# Relay_block_v1_circuit_diagram.net
KiCad netlist of a schematic drawn in EAGLE
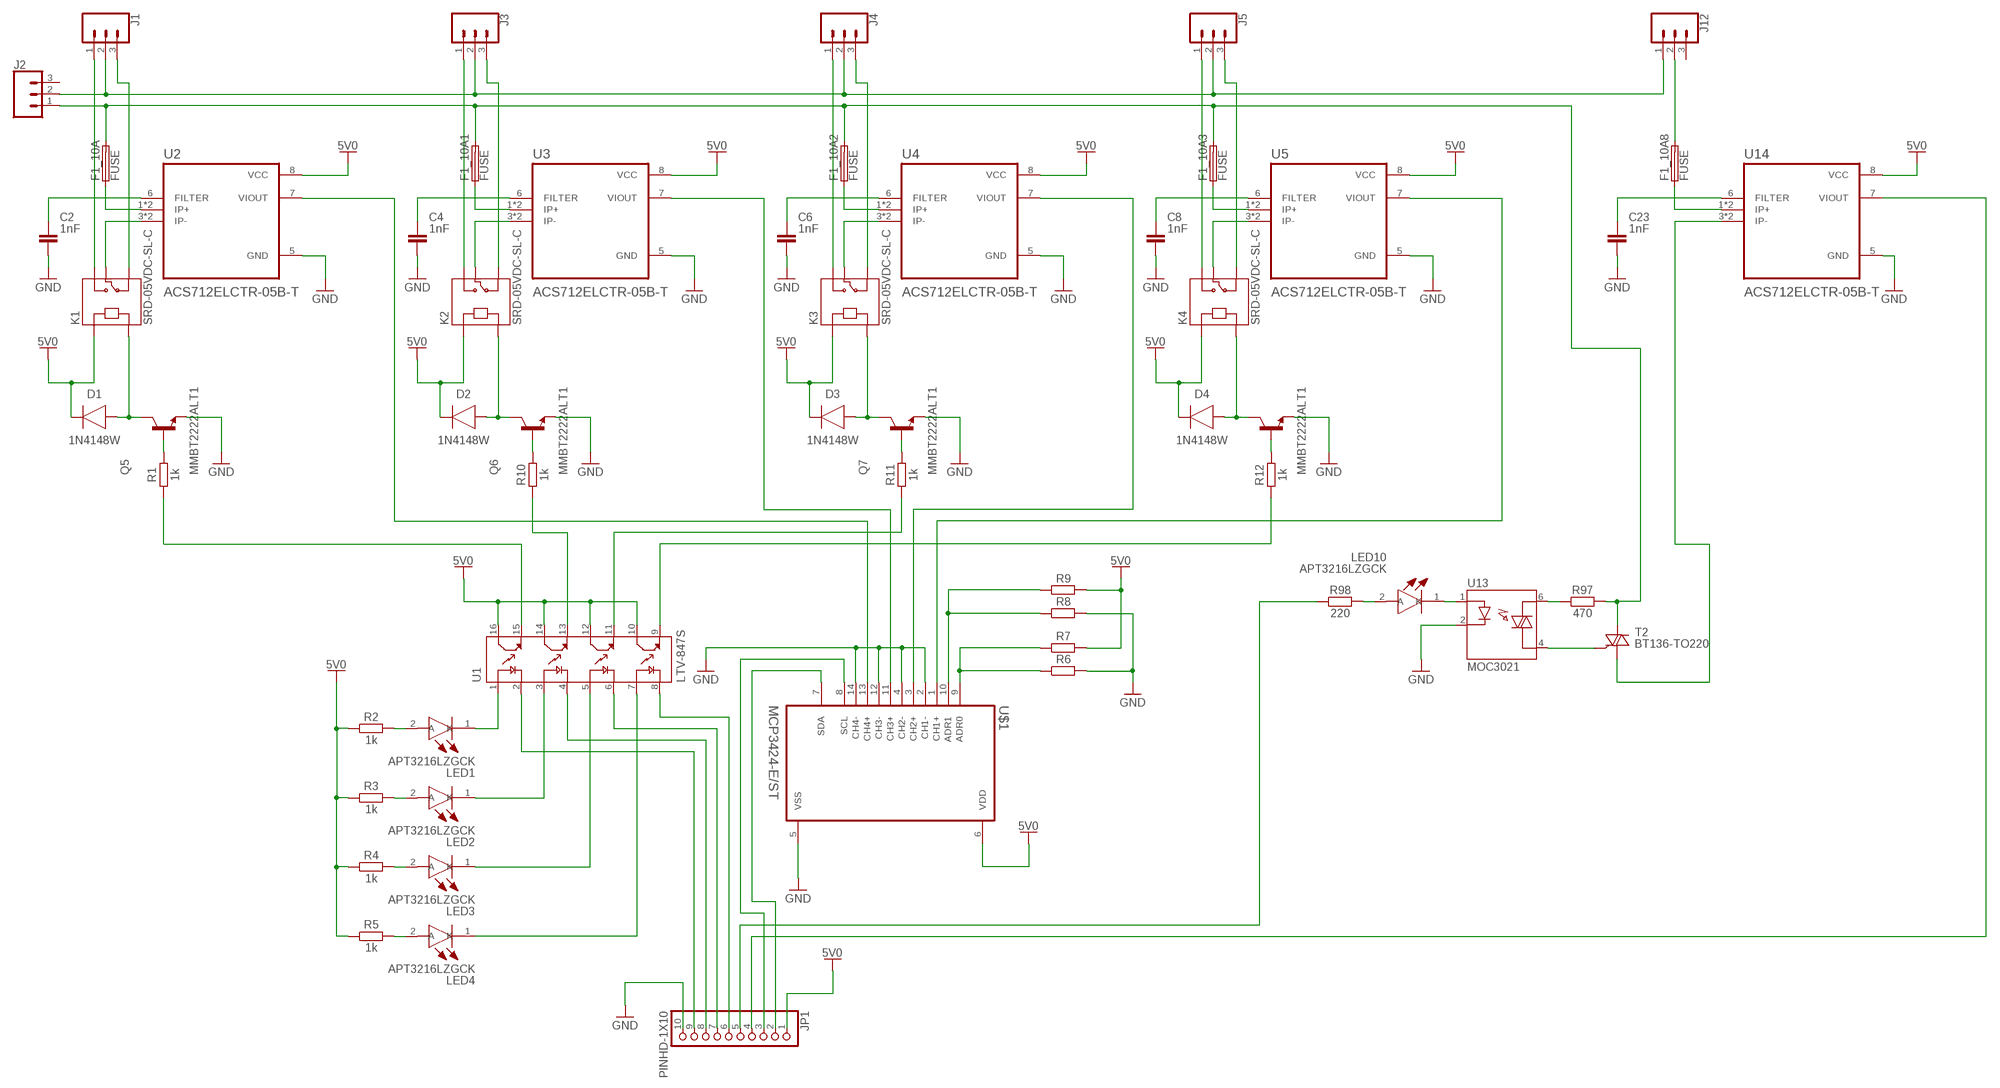
[diagram p0: schematic, sheet 1]

(export (version "E")
  (design (tool "Eeschema 10.0.6"))
  (components
    (comp (ref "C2")
      (value "1nF")
      (footprint "eagle-import:CAPC3216X135")
      (libsource (lib "eagle-import") (part "CCHIP-1206(3216-METRIC)_"))
    )
    (comp (ref "C4")
      (value "1nF")
      (footprint "eagle-import:CAPC3216X135")
      (libsource (lib "eagle-import") (part "CCHIP-1206(3216-METRIC)_"))
    )
    (comp (ref "C6")
      (value "1nF")
      (footprint "eagle-import:CAPC3216X135")
      (libsource (lib "eagle-import") (part "CCHIP-1206(3216-METRIC)_"))
    )
    (comp (ref "C8")
      (value "1nF")
      (footprint "eagle-import:CAPC3216X135")
      (libsource (lib "eagle-import") (part "CCHIP-1206(3216-METRIC)_"))
    )
    (comp (ref "C23")
      (value "1nF")
      (footprint "eagle-import:CAPC3216X135")
      (libsource (lib "eagle-import") (part "CCHIP-1206(3216-METRIC)_"))
    )
    (comp (ref "D1")
      (value "1N4148W")
      (footprint "eagle-import:SOD3715X135")
      (fields (field (name "MANUFACTURER") "Diodes Incorporated"))
      (libsource (lib "eagle-import") (part "DIODE__SOD123G1N4148W-7-F"))
    )
    (comp (ref "D2")
      (value "1N4148W")
      (footprint "eagle-import:SOD3715X135")
      (fields (field (name "MANUFACTURER") "Diodes Incorporated"))
      (libsource (lib "eagle-import") (part "DIODE__SOD123G1N4148W-7-F"))
    )
    (comp (ref "D3")
      (value "1N4148W")
      (footprint "eagle-import:SOD3715X135")
      (fields (field (name "MANUFACTURER") "Diodes Incorporated"))
      (libsource (lib "eagle-import") (part "DIODE__SOD123G1N4148W-7-F"))
    )
    (comp (ref "D4")
      (value "1N4148W")
      (footprint "eagle-import:SOD3715X135")
      (fields (field (name "MANUFACTURER") "Diodes Incorporated"))
      (libsource (lib "eagle-import") (part "DIODE__SOD123G1N4148W-7-F"))
    )
    (comp (ref "F1_10A")
      (value "FUSE")
      (footprint "eagle-import:FUSC3215X82N")
      (libsource (lib "eagle-import") (part "FUSECHIP-1206(3216-METRIC)_"))
    )
    (comp (ref "F1_10A1")
      (value "FUSE")
      (footprint "eagle-import:FUSC3215X82N")
      (libsource (lib "eagle-import") (part "FUSECHIP-1206(3216-METRIC)_"))
    )
    (comp (ref "F1_10A2")
      (value "FUSE")
      (footprint "eagle-import:FUSC3215X82N")
      (libsource (lib "eagle-import") (part "FUSECHIP-1206(3216-METRIC)_"))
    )
    (comp (ref "F1_10A3")
      (value "FUSE")
      (footprint "eagle-import:FUSC3215X82N")
      (libsource (lib "eagle-import") (part "FUSECHIP-1206(3216-METRIC)_"))
    )
    (comp (ref "F1_10A8")
      (value "FUSE")
      (footprint "eagle-import:FUSC3215X82N")
      (libsource (lib "eagle-import") (part "FUSECHIP-1206(3216-METRIC)_"))
    )
    (comp (ref "J1")
      (value "CONN_03-SCREW-5MM")
      (footprint "eagle-import:SCREWTERMINAL-5MM-3")
      (libsource (lib "eagle-import") (part "CONN_03-SCREW-5MM"))
    )
    (comp (ref "J2")
      (value "CONN_03-SCREW-5MM")
      (footprint "eagle-import:SCREWTERMINAL-5MM-3")
      (libsource (lib "eagle-import") (part "CONN_03-SCREW-5MM"))
    )
    (comp (ref "J3")
      (value "CONN_03-SCREW-5MM")
      (footprint "eagle-import:SCREWTERMINAL-5MM-3")
      (libsource (lib "eagle-import") (part "CONN_03-SCREW-5MM"))
    )
    (comp (ref "J4")
      (value "CONN_03-SCREW-5MM")
      (footprint "eagle-import:SCREWTERMINAL-5MM-3")
      (libsource (lib "eagle-import") (part "CONN_03-SCREW-5MM"))
    )
    (comp (ref "J5")
      (value "CONN_03-SCREW-5MM")
      (footprint "eagle-import:SCREWTERMINAL-5MM-3")
      (libsource (lib "eagle-import") (part "CONN_03-SCREW-5MM"))
    )
    (comp (ref "J12")
      (value "CONN_03-SCREW-5MM")
      (footprint "eagle-import:SCREWTERMINAL-5MM-3")
      (libsource (lib "eagle-import") (part "CONN_03-SCREW-5MM"))
    )
    (comp (ref "JP1")
      (value "PINHD-1X10")
      (footprint "eagle-import:1X10")
      (libsource (lib "eagle-import") (part "PINHD-1X10"))
    )
    (comp (ref "K1")
      (value "SRD-05VDC-SL-C")
      (footprint "eagle-import:RELAY_SRD-05VDC-SL-C")
      (fields (field (name "MANUFACTURER") "SONGLE RELAY"))
      (libsource (lib "eagle-import") (part "SRD-05VDC-SL-C"))
    )
    (comp (ref "K2")
      (value "SRD-05VDC-SL-C")
      (footprint "eagle-import:RELAY_SRD-05VDC-SL-C")
      (fields (field (name "MANUFACTURER") "SONGLE RELAY"))
      (libsource (lib "eagle-import") (part "SRD-05VDC-SL-C"))
    )
    (comp (ref "K3")
      (value "SRD-05VDC-SL-C")
      (footprint "eagle-import:RELAY_SRD-05VDC-SL-C")
      (fields (field (name "MANUFACTURER") "SONGLE RELAY"))
      (libsource (lib "eagle-import") (part "SRD-05VDC-SL-C"))
    )
    (comp (ref "K4")
      (value "SRD-05VDC-SL-C")
      (footprint "eagle-import:RELAY_SRD-05VDC-SL-C")
      (fields (field (name "MANUFACTURER") "SONGLE RELAY"))
      (libsource (lib "eagle-import") (part "SRD-05VDC-SL-C"))
    )
    (comp (ref "LED1")
      (value "APT3216LZGCK")
      (footprint "eagle-import:LEDC3216X95N")
      (fields (field (name "MOUSER_PART_NUMBER") "604-APT3216LZGCK"))
      (libsource (lib "eagle-import") (part "APT3216LZGCK"))
    )
    (comp (ref "LED2")
      (value "APT3216LZGCK")
      (footprint "eagle-import:LEDC3216X95N")
      (fields (field (name "MOUSER_PART_NUMBER") "604-APT3216LZGCK"))
      (libsource (lib "eagle-import") (part "APT3216LZGCK"))
    )
    (comp (ref "LED3")
      (value "APT3216LZGCK")
      (footprint "eagle-import:LEDC3216X95N")
      (fields (field (name "MOUSER_PART_NUMBER") "604-APT3216LZGCK"))
      (libsource (lib "eagle-import") (part "APT3216LZGCK"))
    )
    (comp (ref "LED4")
      (value "APT3216LZGCK")
      (footprint "eagle-import:LEDC3216X95N")
      (fields (field (name "MOUSER_PART_NUMBER") "604-APT3216LZGCK"))
      (libsource (lib "eagle-import") (part "APT3216LZGCK"))
    )
    (comp (ref "LED10")
      (value "APT3216LZGCK")
      (footprint "eagle-import:LEDC3216X95N")
      (fields (field (name "MOUSER_PART_NUMBER") "604-APT3216LZGCK"))
      (libsource (lib "eagle-import") (part "APT3216LZGCK"))
    )
    (comp (ref "Q5")
      (value "MMBT2222ALT1")
      (footprint "eagle-import:SOT95P237X111-3N")
      (fields (field (name "MF") "ON Semiconductor"))
      (libsource (lib "eagle-import") (part "MMBT2222ALT1"))
    )
    (comp (ref "Q6")
      (value "MMBT2222ALT1")
      (footprint "eagle-import:SOT95P237X111-3N")
      (fields (field (name "MF") "ON Semiconductor"))
      (libsource (lib "eagle-import") (part "MMBT2222ALT1"))
    )
    (comp (ref "Q7")
      (value "MMBT2222ALT1")
      (footprint "eagle-import:SOT95P237X111-3N")
      (fields (field (name "MF") "ON Semiconductor"))
      (libsource (lib "eagle-import") (part "MMBT2222ALT1"))
    )
    (comp (ref "Q8")
      (value "MMBT2222ALT1")
      (footprint "eagle-import:SOT95P237X111-3N")
      (fields (field (name "MF") "ON Semiconductor"))
      (libsource (lib "eagle-import") (part "MMBT2222ALT1"))
    )
    (comp (ref "R1")
      (value "1k")
      (footprint "eagle-import:RESC3216X70")
      (libsource (lib "eagle-import") (part "RCHIP-1206(3216-METRIC)_"))
    )
    (comp (ref "R2")
      (value "1k")
      (footprint "eagle-import:RESC3216X70")
      (libsource (lib "eagle-import") (part "RCHIP-1206(3216-METRIC)_"))
    )
    (comp (ref "R3")
      (value "1k")
      (footprint "eagle-import:RESC3216X70")
      (libsource (lib "eagle-import") (part "RCHIP-1206(3216-METRIC)_"))
    )
    (comp (ref "R4")
      (value "1k")
      (footprint "eagle-import:RESC3216X70")
      (libsource (lib "eagle-import") (part "RCHIP-1206(3216-METRIC)_"))
    )
    (comp (ref "R5")
      (value "1k")
      (footprint "eagle-import:RESC3216X70")
      (libsource (lib "eagle-import") (part "RCHIP-1206(3216-METRIC)_"))
    )
    (comp (ref "R6")
      (value "R_CHIP-1206(3216-METRIC)")
      (footprint "eagle-import:RESC3216X70")
      (libsource (lib "eagle-import") (part "RCHIP-1206(3216-METRIC)_"))
    )
    (comp (ref "R7")
      (value "R_CHIP-1206(3216-METRIC)")
      (footprint "eagle-import:RESC3216X70")
      (libsource (lib "eagle-import") (part "RCHIP-1206(3216-METRIC)_"))
    )
    (comp (ref "R8")
      (value "R_CHIP-1206(3216-METRIC)")
      (footprint "eagle-import:RESC3216X70")
      (libsource (lib "eagle-import") (part "RCHIP-1206(3216-METRIC)_"))
    )
    (comp (ref "R9")
      (value "R_CHIP-1206(3216-METRIC)")
      (footprint "eagle-import:RESC3216X70")
      (libsource (lib "eagle-import") (part "RCHIP-1206(3216-METRIC)_"))
    )
    (comp (ref "R10")
      (value "1k")
      (footprint "eagle-import:RESC3216X70")
      (libsource (lib "eagle-import") (part "RCHIP-1206(3216-METRIC)_"))
    )
    (comp (ref "R11")
      (value "1k")
      (footprint "eagle-import:RESC3216X70")
      (libsource (lib "eagle-import") (part "RCHIP-1206(3216-METRIC)_"))
    )
    (comp (ref "R12")
      (value "1k")
      (footprint "eagle-import:RESC3216X70")
      (libsource (lib "eagle-import") (part "RCHIP-1206(3216-METRIC)_"))
    )
    (comp (ref "R97")
      (value "470")
      (footprint "eagle-import:RESC3216X70")
      (libsource (lib "eagle-import") (part "RCHIP-1206(3216-METRIC)_"))
    )
    (comp (ref "R98")
      (value "220")
      (footprint "eagle-import:RESC3216X70")
      (libsource (lib "eagle-import") (part "RCHIP-1206(3216-METRIC)_"))
    )
    (comp (ref "T2")
      (value "BT136-TO220")
      (footprint "eagle-import:TO220AB")
      (fields (field (name "MF") "Rectron") (field (name "MP") "BT136"))
      (libsource (lib "eagle-import") (part "BT136-TO220"))
    )
    (comp (ref "U$1")
      (value "MCP3424-E/ST")
      (footprint "eagle-import:SOP65P640X120-14N")
      (libsource (lib "eagle-import") (part "MCP3424-E/ST"))
    )
    (comp (ref "U1")
      (value "LTV-847S")
      (footprint "eagle-import:SOIC254P1016X460-16N")
      (fields (field (name "MANUFACTURER") "LITE-ON Technology"))
      (libsource (lib "eagle-import") (part "LTV-847S"))
    )
    (comp (ref "U2")
      (value "ACS712ELCTR-05B-T")
      (footprint "eagle-import:SOIC127P600X175-8N")
      (libsource (lib "eagle-import") (part "ACS712ELCTR-05B-T"))
    )
    (comp (ref "U3")
      (value "ACS712ELCTR-05B-T")
      (footprint "eagle-import:SOIC127P600X175-8N")
      (libsource (lib "eagle-import") (part "ACS712ELCTR-05B-T"))
    )
    (comp (ref "U4")
      (value "ACS712ELCTR-05B-T")
      (footprint "eagle-import:SOIC127P600X175-8N")
      (libsource (lib "eagle-import") (part "ACS712ELCTR-05B-T"))
    )
    (comp (ref "U5")
      (value "ACS712ELCTR-05B-T")
      (footprint "eagle-import:SOIC127P600X175-8N")
      (libsource (lib "eagle-import") (part "ACS712ELCTR-05B-T"))
    )
    (comp (ref "U13")
      (value "MOC3021")
      (footprint "eagle-import:DIP762W45P254L889H508Q6")
      (fields (field (name "MF") "Lite-On"))
      (libsource (lib "eagle-import") (part "MOC3021"))
    )
    (comp (ref "U14")
      (value "ACS712ELCTR-05B-T")
      (footprint "eagle-import:SOIC127P600X175-8N")
      (libsource (lib "eagle-import") (part "ACS712ELCTR-05B-T"))
    )
  )
  (nets
    (net (code "1") (name "5V0") (class "Default")
      (node (ref "D1") (pin "1") (pinfunction "C_1") (pintype "passive"))
      (node (ref "D2") (pin "1") (pinfunction "C_1") (pintype "passive"))
      (node (ref "D3") (pin "1") (pinfunction "C_1") (pintype "passive"))
      (node (ref "D4") (pin "1") (pinfunction "C_1") (pintype "passive"))
      (node (ref "JP1") (pin "1") (pinfunction "1_1") (pintype "passive"))
      (node (ref "K1") (pin "A1") (pinfunction "A1_A1") (pintype "passive"))
      (node (ref "K2") (pin "A1") (pinfunction "A1_A1") (pintype "passive"))
      (node (ref "K3") (pin "A1") (pinfunction "A1_A1") (pintype "passive"))
      (node (ref "K4") (pin "A1") (pinfunction "A1_A1") (pintype "passive"))
      (node (ref "R2") (pin "1") (pinfunction "1_1") (pintype "passive"))
      (node (ref "R3") (pin "1") (pinfunction "1_1") (pintype "passive"))
      (node (ref "R4") (pin "1") (pinfunction "1_1") (pintype "passive"))
      (node (ref "R5") (pin "1") (pinfunction "1_1") (pintype "passive"))
      (node (ref "R7") (pin "2") (pinfunction "2_2") (pintype "passive"))
      (node (ref "R9") (pin "2") (pinfunction "2_2") (pintype "passive"))
      (node (ref "U$1") (pin "6") (pinfunction "VDD_6") (pintype "power_in"))
      (node (ref "U1") (pin "10") (pinfunction "CT3_10") (pintype "passive"))
      (node (ref "U1") (pin "12") (pinfunction "CT2_12") (pintype "passive"))
      (node (ref "U1") (pin "14") (pinfunction "CT1_14") (pintype "passive"))
      (node (ref "U1") (pin "16") (pinfunction "CT_16") (pintype "passive"))
      (node (ref "U14") (pin "8") (pinfunction "VCC_8") (pintype "power_in"))
      (node (ref "U2") (pin "8") (pinfunction "VCC_8") (pintype "power_in"))
      (node (ref "U3") (pin "8") (pinfunction "VCC_8") (pintype "power_in"))
      (node (ref "U4") (pin "8") (pinfunction "VCC_8") (pintype "power_in"))
      (node (ref "U5") (pin "8") (pinfunction "VCC_8") (pintype "power_in"))
    )
    (net (code "2") (name "GND") (class "Default")
      (node (ref "C2") (pin "2") (pinfunction "2_2") (pintype "passive"))
      (node (ref "C23") (pin "2") (pinfunction "2_2") (pintype "passive"))
      (node (ref "C4") (pin "2") (pinfunction "2_2") (pintype "passive"))
      (node (ref "C6") (pin "2") (pinfunction "2_2") (pintype "passive"))
      (node (ref "C8") (pin "2") (pinfunction "2_2") (pintype "passive"))
      (node (ref "JP1") (pin "10") (pinfunction "10_10") (pintype "passive"))
      (node (ref "Q5") (pin "2") (pinfunction "E_2") (pintype "passive"))
      (node (ref "Q6") (pin "2") (pinfunction "E_2") (pintype "passive"))
      (node (ref "Q7") (pin "2") (pinfunction "E_2") (pintype "passive"))
      (node (ref "Q8") (pin "2") (pinfunction "E_2") (pintype "passive"))
      (node (ref "R6") (pin "2") (pinfunction "2_2") (pintype "passive"))
      (node (ref "R8") (pin "2") (pinfunction "2_2") (pintype "passive"))
      (node (ref "U$1") (pin "12") (pinfunction "CH3-_12") (pintype "input"))
      (node (ref "U$1") (pin "14") (pinfunction "CH4-_14") (pintype "input"))
      (node (ref "U$1") (pin "2") (pinfunction "CH1-_2") (pintype "input"))
      (node (ref "U$1") (pin "4") (pinfunction "CH2-_4") (pintype "input"))
      (node (ref "U$1") (pin "5") (pinfunction "VSS_5") (pintype "power_in"))
      (node (ref "U13") (pin "2") (pinfunction "CATODE_2") (pintype "passive"))
      (node (ref "U14") (pin "5") (pinfunction "GND_5") (pintype "power_in"))
      (node (ref "U2") (pin "5") (pinfunction "GND_5") (pintype "power_in"))
      (node (ref "U3") (pin "5") (pinfunction "GND_5") (pintype "power_in"))
      (node (ref "U4") (pin "5") (pinfunction "GND_5") (pintype "power_in"))
      (node (ref "U5") (pin "5") (pinfunction "GND_5") (pintype "power_in"))
    )
    (net (code "3") (name "Net-(D1-A)") (class "Default")
      (node (ref "D1") (pin "2") (pinfunction "A_2") (pintype "passive"))
      (node (ref "K1") (pin "A2") (pinfunction "A2_A2") (pintype "passive"))
      (node (ref "Q5") (pin "3") (pinfunction "C_3") (pintype "passive"))
    )
    (net (code "4") (name "Net-(D2-A)") (class "Default")
      (node (ref "D2") (pin "2") (pinfunction "A_2") (pintype "passive"))
      (node (ref "K2") (pin "A2") (pinfunction "A2_A2") (pintype "passive"))
      (node (ref "Q6") (pin "3") (pinfunction "C_3") (pintype "passive"))
    )
    (net (code "5") (name "Net-(D3-A)") (class "Default")
      (node (ref "D3") (pin "2") (pinfunction "A_2") (pintype "passive"))
      (node (ref "K3") (pin "A2") (pinfunction "A2_A2") (pintype "passive"))
      (node (ref "Q7") (pin "3") (pinfunction "C_3") (pintype "passive"))
    )
    (net (code "6") (name "Net-(D4-A)") (class "Default")
      (node (ref "D4") (pin "2") (pinfunction "A_2") (pintype "passive"))
      (node (ref "K4") (pin "A2") (pinfunction "A2_A2") (pintype "passive"))
      (node (ref "Q8") (pin "3") (pinfunction "C_3") (pintype "passive"))
    )
    (net (code "7") (name "Net-(F1_10A-Pad1)") (class "Default")
      (node (ref "F1_10A") (pin "1") (pinfunction "1_1") (pintype "passive"))
      (node (ref "U2") (pin "1") (pinfunction "IP+_1") (pintype "input"))
      (node (ref "U2") (pin "2") (pinfunction "IP+_2") (pintype "input"))
    )
    (net (code "8") (name "Net-(F1_10A1-Pad1)") (class "Default")
      (node (ref "F1_10A1") (pin "1") (pinfunction "1_1") (pintype "passive"))
      (node (ref "U3") (pin "1") (pinfunction "IP+_1") (pintype "input"))
      (node (ref "U3") (pin "2") (pinfunction "IP+_2") (pintype "input"))
    )
    (net (code "9") (name "Net-(F1_10A2-Pad1)") (class "Default")
      (node (ref "F1_10A2") (pin "1") (pinfunction "1_1") (pintype "passive"))
      (node (ref "U4") (pin "1") (pinfunction "IP+_1") (pintype "input"))
      (node (ref "U4") (pin "2") (pinfunction "IP+_2") (pintype "input"))
    )
    (net (code "10") (name "Net-(F1_10A3-Pad1)") (class "Default")
      (node (ref "F1_10A3") (pin "1") (pinfunction "1_1") (pintype "passive"))
      (node (ref "U5") (pin "1") (pinfunction "IP+_1") (pintype "input"))
      (node (ref "U5") (pin "2") (pinfunction "IP+_2") (pintype "input"))
    )
    (net (code "11") (name "Net-(F1_10A8-Pad1)") (class "Default")
      (node (ref "F1_10A8") (pin "1") (pinfunction "1_1") (pintype "passive"))
      (node (ref "U14") (pin "1") (pinfunction "IP+_1") (pintype "input"))
      (node (ref "U14") (pin "2") (pinfunction "IP+_2") (pintype "input"))
    )
    (net (code "12") (name "Net-(F1_10A8-Pad2)") (class "Default")
      (node (ref "F1_10A8") (pin "2") (pinfunction "2_2") (pintype "passive"))
      (node (ref "J12") (pin "2") (pinfunction "2_2") (pintype "passive"))
    )
    (net (code "13") (name "Net-(J1-Pad1)") (class "Default")
      (node (ref "J1") (pin "1") (pinfunction "1_1") (pintype "passive"))
      (node (ref "K1") (pin "NO") (pinfunction "NO_NO") (pintype "passive"))
    )
    (net (code "14") (name "Net-(J1-Pad2)") (class "Default")
      (node (ref "J1") (pin "2") (pinfunction "2_2") (pintype "passive"))
      (node (ref "J12") (pin "1") (pinfunction "1_1") (pintype "passive"))
      (node (ref "J2") (pin "2") (pinfunction "2_2") (pintype "passive"))
      (node (ref "J3") (pin "2") (pinfunction "2_2") (pintype "passive"))
      (node (ref "J4") (pin "2") (pinfunction "2_2") (pintype "passive"))
      (node (ref "J5") (pin "2") (pinfunction "2_2") (pintype "passive"))
    )
    (net (code "15") (name "Net-(J1-Pad3)") (class "Default")
      (node (ref "J1") (pin "3") (pinfunction "3_3") (pintype "passive"))
      (node (ref "K1") (pin "NC") (pinfunction "NC_NC") (pintype "passive"))
    )
    (net (code "16") (name "Net-(J3-Pad1)") (class "Default")
      (node (ref "J3") (pin "1") (pinfunction "1_1") (pintype "passive"))
      (node (ref "K2") (pin "NO") (pinfunction "NO_NO") (pintype "passive"))
    )
    (net (code "17") (name "Net-(J3-Pad3)") (class "Default")
      (node (ref "J3") (pin "3") (pinfunction "3_3") (pintype "passive"))
      (node (ref "K2") (pin "NC") (pinfunction "NC_NC") (pintype "passive"))
    )
    (net (code "18") (name "Net-(J4-Pad1)") (class "Default")
      (node (ref "J4") (pin "1") (pinfunction "1_1") (pintype "passive"))
      (node (ref "K3") (pin "NO") (pinfunction "NO_NO") (pintype "passive"))
    )
    (net (code "19") (name "Net-(J4-Pad3)") (class "Default")
      (node (ref "J4") (pin "3") (pinfunction "3_3") (pintype "passive"))
      (node (ref "K3") (pin "NC") (pinfunction "NC_NC") (pintype "passive"))
    )
    (net (code "20") (name "Net-(J5-Pad1)") (class "Default")
      (node (ref "J5") (pin "1") (pinfunction "1_1") (pintype "passive"))
      (node (ref "K4") (pin "NO") (pinfunction "NO_NO") (pintype "passive"))
    )
    (net (code "21") (name "Net-(J5-Pad3)") (class "Default")
      (node (ref "J5") (pin "3") (pinfunction "3_3") (pintype "passive"))
      (node (ref "K4") (pin "NC") (pinfunction "NC_NC") (pintype "passive"))
    )
    (net (code "22") (name "Net-(JP1-Pad5)") (class "Default")
      (node (ref "JP1") (pin "5") (pinfunction "5_5") (pintype "passive"))
      (node (ref "R98") (pin "1") (pinfunction "1_1") (pintype "passive"))
    )
    (net (code "23") (name "Net-(K1-PadCOM)") (class "Default")
      (node (ref "K1") (pin "COM") (pinfunction "COM_COM") (pintype "passive"))
      (node (ref "U2") (pin "3") (pinfunction "IP-_3") (pintype "input"))
      (node (ref "U2") (pin "4") (pinfunction "IP-_4") (pintype "input"))
    )
    (net (code "24") (name "Net-(K2-PadCOM)") (class "Default")
      (node (ref "K2") (pin "COM") (pinfunction "COM_COM") (pintype "passive"))
      (node (ref "U3") (pin "3") (pinfunction "IP-_3") (pintype "input"))
      (node (ref "U3") (pin "4") (pinfunction "IP-_4") (pintype "input"))
    )
    (net (code "25") (name "Net-(K3-PadCOM)") (class "Default")
      (node (ref "K3") (pin "COM") (pinfunction "COM_COM") (pintype "passive"))
      (node (ref "U4") (pin "3") (pinfunction "IP-_3") (pintype "input"))
      (node (ref "U4") (pin "4") (pinfunction "IP-_4") (pintype "input"))
    )
    (net (code "26") (name "Net-(K4-PadCOM)") (class "Default")
      (node (ref "K4") (pin "COM") (pinfunction "COM_COM") (pintype "passive"))
      (node (ref "U5") (pin "3") (pinfunction "IP-_3") (pintype "input"))
      (node (ref "U5") (pin "4") (pinfunction "IP-_4") (pintype "input"))
    )
    (net (code "27") (name "Net-(LED1-A)") (class "Default")
      (node (ref "LED1") (pin "2") (pinfunction "A_2") (pintype "bidirectional"))
      (node (ref "R2") (pin "2") (pinfunction "2_2") (pintype "passive"))
    )
    (net (code "28") (name "Net-(LED1-K)") (class "Default")
      (node (ref "LED1") (pin "1") (pinfunction "K_1") (pintype "bidirectional"))
      (node (ref "U1") (pin "1") (pinfunction "A_1") (pintype "passive"))
    )
    (net (code "29") (name "Net-(LED2-A)") (class "Default")
      (node (ref "LED2") (pin "2") (pinfunction "A_2") (pintype "bidirectional"))
      (node (ref "R3") (pin "2") (pinfunction "2_2") (pintype "passive"))
    )
    (net (code "30") (name "Net-(LED2-K)") (class "Default")
      (node (ref "LED2") (pin "1") (pinfunction "K_1") (pintype "bidirectional"))
      (node (ref "U1") (pin "3") (pinfunction "A1_3") (pintype "passive"))
    )
    (net (code "31") (name "Net-(LED3-A)") (class "Default")
      (node (ref "LED3") (pin "2") (pinfunction "A_2") (pintype "bidirectional"))
      (node (ref "R4") (pin "2") (pinfunction "2_2") (pintype "passive"))
    )
    (net (code "32") (name "Net-(LED3-K)") (class "Default")
      (node (ref "LED3") (pin "1") (pinfunction "K_1") (pintype "bidirectional"))
      (node (ref "U1") (pin "5") (pinfunction "A2_5") (pintype "passive"))
    )
    (net (code "33") (name "Net-(LED4-A)") (class "Default")
      (node (ref "LED4") (pin "2") (pinfunction "A_2") (pintype "bidirectional"))
      (node (ref "R5") (pin "2") (pinfunction "2_2") (pintype "passive"))
    )
    (net (code "34") (name "Net-(LED4-K)") (class "Default")
      (node (ref "LED4") (pin "1") (pinfunction "K_1") (pintype "bidirectional"))
      (node (ref "U1") (pin "7") (pinfunction "A3_7") (pintype "passive"))
    )
    (net (code "35") (name "Net-(LED10-A)") (class "Default")
      (node (ref "LED10") (pin "2") (pinfunction "A_2") (pintype "bidirectional"))
      (node (ref "R98") (pin "2") (pinfunction "2_2") (pintype "passive"))
    )
    (net (code "36") (name "Net-(LED10-K)") (class "Default")
      (node (ref "LED10") (pin "1") (pinfunction "K_1") (pintype "bidirectional"))
      (node (ref "U13") (pin "1") (pinfunction "ANODE_1") (pintype "passive"))
    )
    (net (code "37") (name "Net-(Q5-B)") (class "Default")
      (node (ref "Q5") (pin "1") (pinfunction "B_1") (pintype "passive"))
      (node (ref "R1") (pin "2") (pinfunction "2_2") (pintype "passive"))
    )
    (net (code "38") (name "Net-(Q6-B)") (class "Default")
      (node (ref "Q6") (pin "1") (pinfunction "B_1") (pintype "passive"))
      (node (ref "R10") (pin "2") (pinfunction "2_2") (pintype "passive"))
    )
    (net (code "39") (name "Net-(Q7-B)") (class "Default")
      (node (ref "Q7") (pin "1") (pinfunction "B_1") (pintype "passive"))
      (node (ref "R11") (pin "2") (pinfunction "2_2") (pintype "passive"))
    )
    (net (code "40") (name "Net-(Q8-B)") (class "Default")
      (node (ref "Q8") (pin "1") (pinfunction "B_1") (pintype "passive"))
      (node (ref "R12") (pin "2") (pinfunction "2_2") (pintype "passive"))
    )
    (net (code "41") (name "Net-(T2-A1)") (class "Default")
      (node (ref "T2") (pin "1") (pinfunction "A1_1") (pintype "passive"))
      (node (ref "U14") (pin "3") (pinfunction "IP-_3") (pintype "input"))
      (node (ref "U14") (pin "4") (pinfunction "IP-_4") (pintype "input"))
    )
    (net (code "42") (name "Net-(T2-A2)") (class "Default")
      (node (ref "F1_10A") (pin "2") (pinfunction "2_2") (pintype "passive"))
      (node (ref "F1_10A1") (pin "2") (pinfunction "2_2") (pintype "passive"))
      (node (ref "F1_10A2") (pin "2") (pinfunction "2_2") (pintype "passive"))
      (node (ref "F1_10A3") (pin "2") (pinfunction "2_2") (pintype "passive"))
      (node (ref "J2") (pin "1") (pinfunction "1_1") (pintype "passive"))
      (node (ref "R97") (pin "2") (pinfunction "2_2") (pintype "passive"))
      (node (ref "T2") (pin "2") (pinfunction "A2_2") (pintype "passive"))
    )
    (net (code "43") (name "Net-(T2-G)") (class "Default")
      (node (ref "T2") (pin "3") (pinfunction "G_3") (pintype "passive"))
      (node (ref "U13") (pin "4") (pinfunction "MAIN_TERM2_4") (pintype "passive"))
    )
    (net (code "44") (name "Net-(U$1-ADR0)") (class "Default")
      (node (ref "R6") (pin "1") (pinfunction "1_1") (pintype "passive"))
      (node (ref "R7") (pin "1") (pinfunction "1_1") (pintype "passive"))
      (node (ref "U$1") (pin "9") (pinfunction "ADR0_9") (pintype "input"))
    )
    (net (code "45") (name "Net-(U$1-ADR1)") (class "Default")
      (node (ref "R8") (pin "1") (pinfunction "1_1") (pintype "passive"))
      (node (ref "R9") (pin "1") (pinfunction "1_1") (pintype "passive"))
      (node (ref "U$1") (pin "10") (pinfunction "ADR1_10") (pintype "input"))
    )
    (net (code "46") (name "Net-(U$1-CH1+)") (class "Default")
      (node (ref "U$1") (pin "1") (pinfunction "CH1+_1") (pintype "input"))
      (node (ref "U5") (pin "7") (pinfunction "VIOUT_7") (pintype "output"))
    )
    (net (code "47") (name "Net-(U$1-CH2+)") (class "Default")
      (node (ref "U$1") (pin "3") (pinfunction "CH2+_3") (pintype "input"))
      (node (ref "U4") (pin "7") (pinfunction "VIOUT_7") (pintype "output"))
    )
    (net (code "48") (name "Net-(U$1-CH3+)") (class "Default")
      (node (ref "U$1") (pin "11") (pinfunction "CH3+_11") (pintype "input"))
      (node (ref "U3") (pin "7") (pinfunction "VIOUT_7") (pintype "output"))
    )
    (net (code "49") (name "Net-(U$1-CH4+)") (class "Default")
      (node (ref "U$1") (pin "13") (pinfunction "CH4+_13") (pintype "input"))
      (node (ref "U2") (pin "7") (pinfunction "VIOUT_7") (pintype "output"))
    )
    (net (code "50") (name "Net-(U$1-SCL)") (class "Default")
      (node (ref "JP1") (pin "3") (pinfunction "3_3") (pintype "passive"))
      (node (ref "U$1") (pin "8") (pinfunction "SCL_8") (pintype "input"))
    )
    (net (code "51") (name "Net-(U$1-SDA)") (class "Default")
      (node (ref "JP1") (pin "2") (pinfunction "2_2") (pintype "passive"))
      (node (ref "U$1") (pin "7") (pinfunction "SDA_7") (pintype "bidirectional"))
    )
    (net (code "52") (name "Net-(U1-C)") (class "Default")
      (node (ref "JP1") (pin "9") (pinfunction "9_9") (pintype "passive"))
      (node (ref "U1") (pin "2") (pinfunction "C_2") (pintype "passive"))
    )
    (net (code "53") (name "Net-(U1-C1)") (class "Default")
      (node (ref "JP1") (pin "8") (pinfunction "8_8") (pintype "passive"))
      (node (ref "U1") (pin "4") (pinfunction "C1_4") (pintype "passive"))
    )
    (net (code "54") (name "Net-(U1-C2)") (class "Default")
      (node (ref "JP1") (pin "7") (pinfunction "7_7") (pintype "passive"))
      (node (ref "U1") (pin "6") (pinfunction "C2_6") (pintype "passive"))
    )
    (net (code "55") (name "Net-(U1-C3)") (class "Default")
      (node (ref "JP1") (pin "6") (pinfunction "6_6") (pintype "passive"))
      (node (ref "U1") (pin "8") (pinfunction "C3_8") (pintype "passive"))
    )
    (net (code "56") (name "Net-(U1-ET)") (class "Default")
      (node (ref "R1") (pin "1") (pinfunction "1_1") (pintype "passive"))
      (node (ref "U1") (pin "15") (pinfunction "ET_15") (pintype "passive"))
    )
    (net (code "57") (name "Net-(U1-ET1)") (class "Default")
      (node (ref "R10") (pin "1") (pinfunction "1_1") (pintype "passive"))
      (node (ref "U1") (pin "13") (pinfunction "ET1_13") (pintype "passive"))
    )
    (net (code "58") (name "Net-(U1-ET2)") (class "Default")
      (node (ref "R11") (pin "1") (pinfunction "1_1") (pintype "passive"))
      (node (ref "U1") (pin "11") (pinfunction "ET2_11") (pintype "passive"))
    )
    (net (code "59") (name "Net-(U1-ET3)") (class "Default")
      (node (ref "R12") (pin "1") (pinfunction "1_1") (pintype "passive"))
      (node (ref "U1") (pin "9") (pinfunction "ET3_9") (pintype "passive"))
    )
    (net (code "60") (name "Net-(U2-FILTER)") (class "Default")
      (node (ref "C2") (pin "1") (pinfunction "1_1") (pintype "passive"))
      (node (ref "U2") (pin "6") (pinfunction "FILTER_6") (pintype "input"))
    )
    (net (code "61") (name "Net-(U3-FILTER)") (class "Default")
      (node (ref "C4") (pin "1") (pinfunction "1_1") (pintype "passive"))
      (node (ref "U3") (pin "6") (pinfunction "FILTER_6") (pintype "input"))
    )
    (net (code "62") (name "Net-(U4-FILTER)") (class "Default")
      (node (ref "C6") (pin "1") (pinfunction "1_1") (pintype "passive"))
      (node (ref "U4") (pin "6") (pinfunction "FILTER_6") (pintype "input"))
    )
    (net (code "63") (name "Net-(U5-FILTER)") (class "Default")
      (node (ref "C8") (pin "1") (pinfunction "1_1") (pintype "passive"))
      (node (ref "U5") (pin "6") (pinfunction "FILTER_6") (pintype "input"))
    )
    (net (code "64") (name "Net-(U13-MAIN_TERM1)") (class "Default")
      (node (ref "R97") (pin "1") (pinfunction "1_1") (pintype "passive"))
      (node (ref "U13") (pin "6") (pinfunction "MAIN_TERM1_6") (pintype "passive"))
    )
    (net (code "65") (name "Net-(U14-FILTER)") (class "Default")
      (node (ref "C23") (pin "1") (pinfunction "1_1") (pintype "passive"))
      (node (ref "U14") (pin "6") (pinfunction "FILTER_6") (pintype "input"))
    )
    (net (code "66") (name "Net-(U14-VIOUT)") (class "Default")
      (node (ref "JP1") (pin "4") (pinfunction "4_4") (pintype "passive"))
      (node (ref "U14") (pin "7") (pinfunction "VIOUT_7") (pintype "output"))
    )
    (net (code "67") (name "unconnected-(J2-Pad3)") (class "Default")
      (node (ref "J2") (pin "3") (pinfunction "3_3") (pintype "passive"))
    )
    (net (code "68") (name "unconnected-(J12-Pad3)") (class "Default")
      (node (ref "J12") (pin "3") (pinfunction "3_3") (pintype "passive"))
    )
  )
)
